# sensori_di_linea_soccer_2018.net
KiCad netlist of a schematic drawn in EAGLE
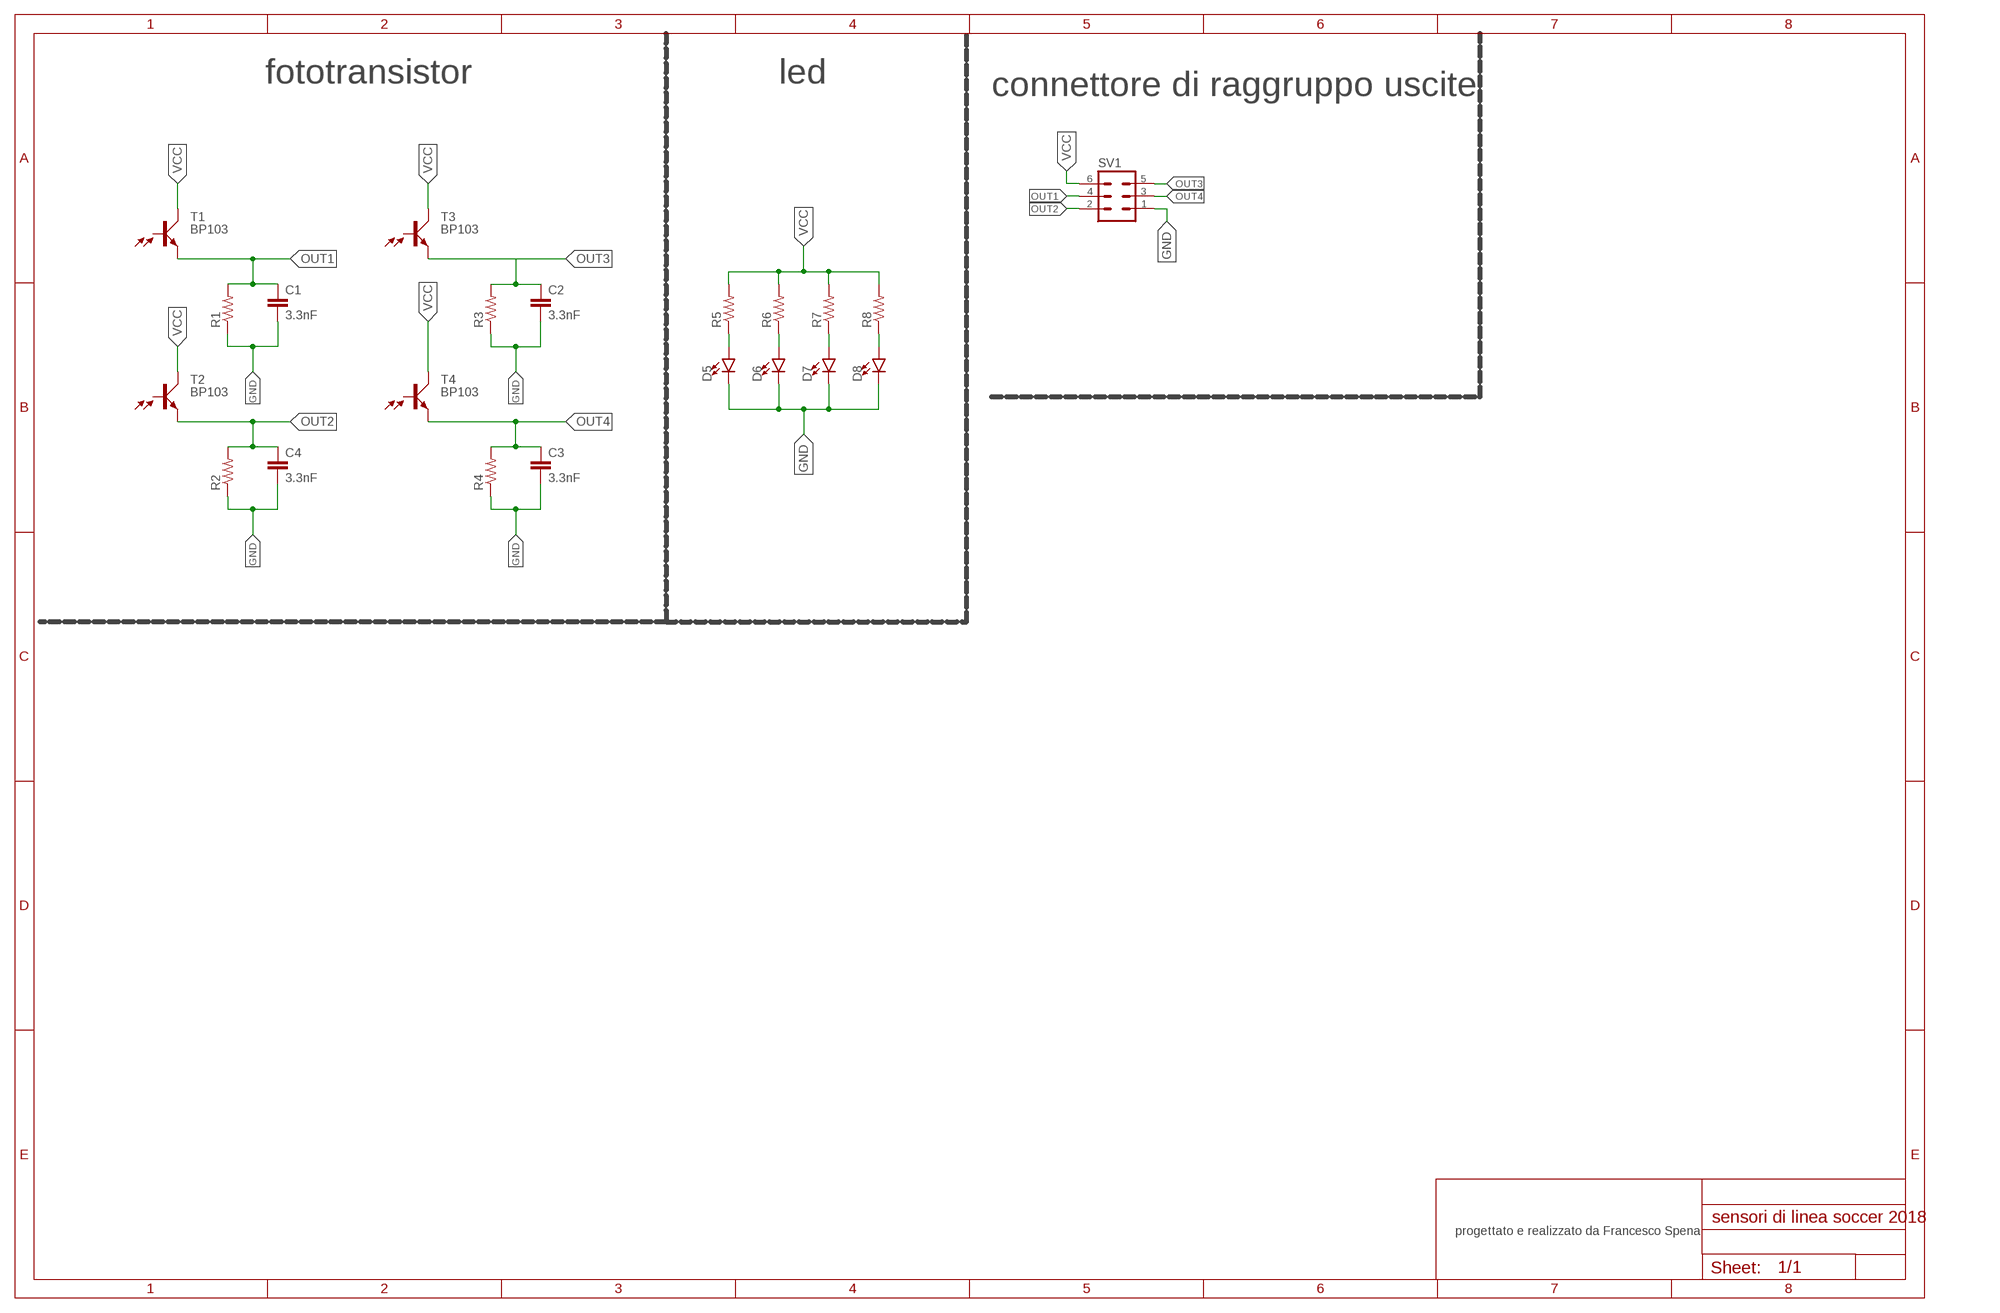
[diagram p0: schematic, sheet 1]

(export (version "E")
  (design (tool "Eeschema 10.0.6"))
  (components
    (comp (ref "C1")
      (value "3.3nF")
      (footprint "eagle-import:0603")
      (libsource (lib "eagle-import") (part "3.3NF-0603-100V-10%"))
    )
    (comp (ref "C2")
      (value "3.3nF")
      (footprint "eagle-import:0603")
      (libsource (lib "eagle-import") (part "3.3NF-0603-100V-10%"))
    )
    (comp (ref "C3")
      (value "3.3nF")
      (footprint "eagle-import:0603")
      (libsource (lib "eagle-import") (part "3.3NF-0603-100V-10%"))
    )
    (comp (ref "C4")
      (value "3.3nF")
      (footprint "eagle-import:0603")
      (libsource (lib "eagle-import") (part "3.3NF-0603-100V-10%"))
    )
    (comp (ref "D5")
      (value "LED3MM")
      (footprint "eagle-import:LED_3MM")
      (libsource (lib "eagle-import") (part "LED3MM"))
    )
    (comp (ref "D6")
      (value "LED3MM")
      (footprint "eagle-import:LED_3MM")
      (libsource (lib "eagle-import") (part "LED3MM"))
    )
    (comp (ref "D7")
      (value "LED3MM")
      (footprint "eagle-import:LED_3MM")
      (libsource (lib "eagle-import") (part "LED3MM"))
    )
    (comp (ref "D8")
      (value "LED3MM")
      (footprint "eagle-import:LED_3MM")
      (libsource (lib "eagle-import") (part "LED3MM"))
    )
    (comp (ref "R1")
      (value "R-US_0204/7")
      (footprint "eagle-import:0204_7")
      (libsource (lib "eagle-import") (part "resistor_348_R-US_0204/7"))
    )
    (comp (ref "R2")
      (value "R-US_0204/7")
      (footprint "eagle-import:0204_7")
      (libsource (lib "eagle-import") (part "resistor_348_R-US_0204/7"))
    )
    (comp (ref "R3")
      (value "R-US_0204/7")
      (footprint "eagle-import:0204_7")
      (libsource (lib "eagle-import") (part "resistor_348_R-US_0204/7"))
    )
    (comp (ref "R4")
      (value "R-US_0204/7")
      (footprint "eagle-import:0204_7")
      (libsource (lib "eagle-import") (part "resistor_348_R-US_0204/7"))
    )
    (comp (ref "R5")
      (value "R-US_0204/7")
      (footprint "eagle-import:0204_7")
      (libsource (lib "eagle-import") (part "R-US_0204/7"))
    )
    (comp (ref "R6")
      (value "R-US_0204/7")
      (footprint "eagle-import:0204_7")
      (libsource (lib "eagle-import") (part "R-US_0204/7"))
    )
    (comp (ref "R7")
      (value "R-US_0204/7")
      (footprint "eagle-import:0204_7")
      (libsource (lib "eagle-import") (part "R-US_0204/7"))
    )
    (comp (ref "R8")
      (value "R-US_0204/7")
      (footprint "eagle-import:0204_7")
      (libsource (lib "eagle-import") (part "R-US_0204/7"))
    )
    (comp (ref "SV1")
      (value "MA03-2")
      (footprint "eagle-import:MA03-2")
      (libsource (lib "eagle-import") (part "MA03-2"))
    )
    (comp (ref "T1")
      (value "BP103")
      (footprint "eagle-import:BP103")
      (libsource (lib "eagle-import") (part "BP103"))
    )
    (comp (ref "T2")
      (value "BP103")
      (footprint "eagle-import:BP103")
      (libsource (lib "eagle-import") (part "BP103"))
    )
    (comp (ref "T3")
      (value "BP103")
      (footprint "eagle-import:BP103")
      (libsource (lib "eagle-import") (part "BP103"))
    )
    (comp (ref "T4")
      (value "BP103")
      (footprint "eagle-import:BP103")
      (libsource (lib "eagle-import") (part "BP103"))
    )
  )
  (nets
    (net (code "1") (name "GND") (class "Default")
      (node (ref "C1") (pin "2") (pinfunction "2_2") (pintype "passive"))
      (node (ref "C2") (pin "2") (pinfunction "2_2") (pintype "passive"))
      (node (ref "C3") (pin "2") (pinfunction "2_2") (pintype "passive"))
      (node (ref "C4") (pin "2") (pinfunction "2_2") (pintype "passive"))
      (node (ref "D5") (pin "K") (pinfunction "C_K") (pintype "passive"))
      (node (ref "D6") (pin "K") (pinfunction "C_K") (pintype "passive"))
      (node (ref "D7") (pin "K") (pinfunction "C_K") (pintype "passive"))
      (node (ref "D8") (pin "K") (pinfunction "C_K") (pintype "passive"))
      (node (ref "R1") (pin "1") (pinfunction "1_1") (pintype "passive"))
      (node (ref "R2") (pin "1") (pinfunction "1_1") (pintype "passive"))
      (node (ref "R3") (pin "1") (pinfunction "1_1") (pintype "passive"))
      (node (ref "R4") (pin "1") (pinfunction "1_1") (pintype "passive"))
      (node (ref "SV1") (pin "1") (pinfunction "1_1") (pintype "passive"))
    )
    (net (code "2") (name "Net-(D5-PadA)") (class "Default")
      (node (ref "D5") (pin "A") (pinfunction "A_A") (pintype "passive"))
      (node (ref "R5") (pin "1") (pinfunction "1_1") (pintype "passive"))
    )
    (net (code "3") (name "Net-(D6-PadA)") (class "Default")
      (node (ref "D6") (pin "A") (pinfunction "A_A") (pintype "passive"))
      (node (ref "R6") (pin "1") (pinfunction "1_1") (pintype "passive"))
    )
    (net (code "4") (name "Net-(D7-PadA)") (class "Default")
      (node (ref "D7") (pin "A") (pinfunction "A_A") (pintype "passive"))
      (node (ref "R7") (pin "1") (pinfunction "1_1") (pintype "passive"))
    )
    (net (code "5") (name "Net-(D8-PadA)") (class "Default")
      (node (ref "D8") (pin "A") (pinfunction "A_A") (pintype "passive"))
      (node (ref "R8") (pin "1") (pinfunction "1_1") (pintype "passive"))
    )
    (net (code "6") (name "OUT1") (class "Default")
      (node (ref "C1") (pin "1") (pinfunction "1_1") (pintype "passive"))
      (node (ref "R1") (pin "2") (pinfunction "2_2") (pintype "passive"))
      (node (ref "SV1") (pin "4") (pinfunction "4_4") (pintype "passive"))
      (node (ref "T1") (pin "E") (pinfunction "E_E") (pintype "passive"))
    )
    (net (code "7") (name "OUT2") (class "Default")
      (node (ref "C4") (pin "1") (pinfunction "1_1") (pintype "passive"))
      (node (ref "R2") (pin "2") (pinfunction "2_2") (pintype "passive"))
      (node (ref "SV1") (pin "2") (pinfunction "2_2") (pintype "passive"))
      (node (ref "T2") (pin "E") (pinfunction "E_E") (pintype "passive"))
    )
    (net (code "8") (name "OUT3") (class "Default")
      (node (ref "C2") (pin "1") (pinfunction "1_1") (pintype "passive"))
      (node (ref "R3") (pin "2") (pinfunction "2_2") (pintype "passive"))
      (node (ref "SV1") (pin "5") (pinfunction "5_5") (pintype "passive"))
      (node (ref "T3") (pin "E") (pinfunction "E_E") (pintype "passive"))
    )
    (net (code "9") (name "OUT4") (class "Default")
      (node (ref "C3") (pin "1") (pinfunction "1_1") (pintype "passive"))
      (node (ref "R4") (pin "2") (pinfunction "2_2") (pintype "passive"))
      (node (ref "SV1") (pin "3") (pinfunction "3_3") (pintype "passive"))
      (node (ref "T4") (pin "E") (pinfunction "E_E") (pintype "passive"))
    )
    (net (code "10") (name "VCC") (class "Default")
      (node (ref "R5") (pin "2") (pinfunction "2_2") (pintype "passive"))
      (node (ref "R6") (pin "2") (pinfunction "2_2") (pintype "passive"))
      (node (ref "R7") (pin "2") (pinfunction "2_2") (pintype "passive"))
      (node (ref "R8") (pin "2") (pinfunction "2_2") (pintype "passive"))
      (node (ref "SV1") (pin "6") (pinfunction "6_6") (pintype "passive"))
      (node (ref "T1") (pin "C") (pinfunction "C_C") (pintype "passive"))
      (node (ref "T2") (pin "C") (pinfunction "C_C") (pintype "passive"))
      (node (ref "T3") (pin "C") (pinfunction "C_C") (pintype "passive"))
      (node (ref "T4") (pin "C") (pinfunction "C_C") (pintype "passive"))
    )
    (net (code "11") (name "unconnected-(T1-PadB)") (class "Default")
      (node (ref "T1") (pin "B") (pinfunction "B_B") (pintype "passive"))
    )
    (net (code "12") (name "unconnected-(T2-PadB)") (class "Default")
      (node (ref "T2") (pin "B") (pinfunction "B_B") (pintype "passive"))
    )
    (net (code "13") (name "unconnected-(T3-PadB)") (class "Default")
      (node (ref "T3") (pin "B") (pinfunction "B_B") (pintype "passive"))
    )
    (net (code "14") (name "unconnected-(T4-PadB)") (class "Default")
      (node (ref "T4") (pin "B") (pinfunction "B_B") (pintype "passive"))
    )
  )
)
